# espurna.net
KiCad netlist of a schematic drawn in EAGLE
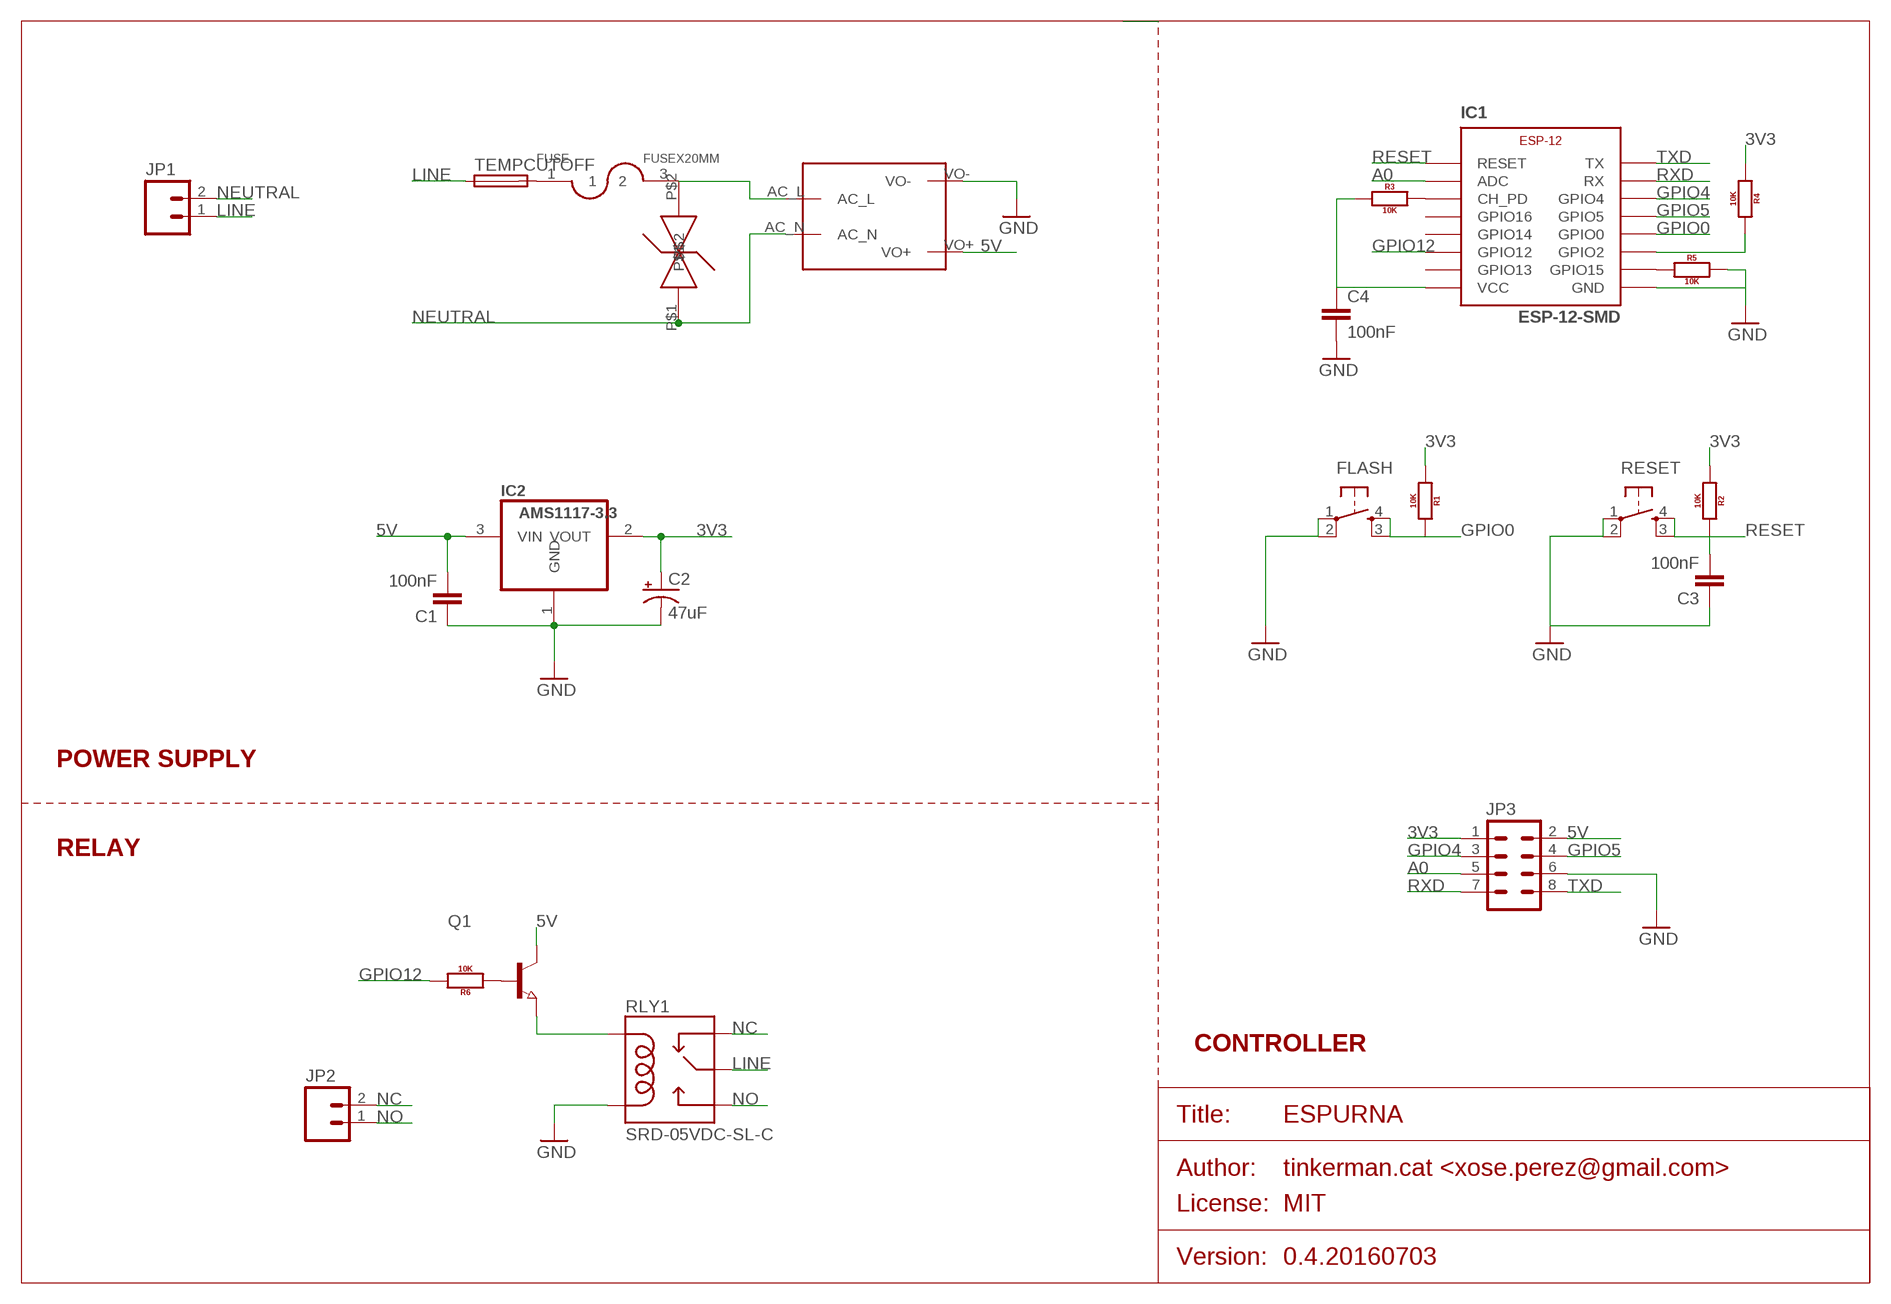
[diagram p0: schematic, sheet 1]

(export (version "E")
  (design (tool "Eeschema 10.0.6"))
  (components
    (comp (ref "C1")
      (value "100nF")
      (footprint "eagle-import:0805")
      (libsource (lib "eagle-import") (part "C-EU0805"))
    )
    (comp (ref "C2")
      (value "47uF")
      (footprint "eagle-import:PANASONIC_C")
      (libsource (lib "eagle-import") (part "CAP_POLC"))
    )
    (comp (ref "C3")
      (value "100nF")
      (footprint "eagle-import:0805")
      (libsource (lib "eagle-import") (part "C-EU0805"))
    )
    (comp (ref "C4")
      (value "100nF")
      (footprint "eagle-import:0805")
      (libsource (lib "eagle-import") (part "C-EU0805"))
    )
    (comp (ref "FLASH")
      (value "TACTILE_BUTTON_SMD")
      (footprint "eagle-import:TACTILE-BUTTON-SMD")
      (libsource (lib "eagle-import") (part "TACTILE_BUTTON_SMD"))
    )
    (comp (ref "FUSE")
      (value "FUSEX20MM")
      (footprint "eagle-import:FUSE_5MM")
      (libsource (lib "eagle-import") (part "FUSEX20MM"))
    )
    (comp (ref "IC1")
      (value "ESP-12-SMD")
      (footprint "eagle-import:ESP-12-SMD")
      (libsource (lib "eagle-import") (part "ESP-12-SMD"))
    )
    (comp (ref "IC2")
      (value "AMS1117-3.3")
      (footprint "eagle-import:SOT223")
      (fields (field (name "MPN") "REG1117"))
      (libsource (lib "eagle-import") (part "REG1117"))
    )
    (comp (ref "JP1")
      (value "M02200MIL")
      (footprint "eagle-import:SCREWTERMINAL-200MIL-2")
      (libsource (lib "eagle-import") (part "M02200MIL"))
    )
    (comp (ref "JP2")
      (value "M02200MIL")
      (footprint "eagle-import:SCREWTERMINAL-200MIL-2")
      (libsource (lib "eagle-import") (part "M02200MIL"))
    )
    (comp (ref "JP3")
      (value "M04X2")
      (footprint "eagle-import:2X4")
      (libsource (lib "eagle-import") (part "M04X2"))
    )
    (comp (ref "Q1")
      (value "NPN-TRANSISTOR_SOT23")
      (footprint "eagle-import:SOT23")
      (libsource (lib "eagle-import") (part "NPN-TRANSISTOR_SOT23"))
    )
    (comp (ref "R1")
      (value "10K")
      (footprint "eagle-import:0805")
      (libsource (lib "eagle-import") (part "RESISTOR0805"))
    )
    (comp (ref "R2")
      (value "10K")
      (footprint "eagle-import:0805")
      (libsource (lib "eagle-import") (part "RESISTOR0805"))
    )
    (comp (ref "R3")
      (value "10K")
      (footprint "eagle-import:0805")
      (libsource (lib "eagle-import") (part "RESISTOR0805"))
    )
    (comp (ref "R4")
      (value "10K")
      (footprint "eagle-import:0805")
      (libsource (lib "eagle-import") (part "RESISTOR0805"))
    )
    (comp (ref "R5")
      (value "10K")
      (footprint "eagle-import:0805")
      (libsource (lib "eagle-import") (part "RESISTOR0805"))
    )
    (comp (ref "R6")
      (value "10K")
      (footprint "eagle-import:0805")
      (libsource (lib "eagle-import") (part "RESISTOR0805"))
    )
    (comp (ref "RESET")
      (value "TACTILE_BUTTON_SMD")
      (footprint "eagle-import:TACTILE-BUTTON-SMD")
      (libsource (lib "eagle-import") (part "TACTILE_BUTTON_SMD"))
    )
    (comp (ref "RLY1")
      (value "SRD-05VDC-SL-C")
      (footprint "eagle-import:SRD-5VDC-SL-C")
      (libsource (lib "eagle-import") (part "RELAYSONGLE"))
    )
    (comp (ref "TEMPCUTOFF")
      (value "PICOFUSE")
      (footprint "eagle-import:PICOFUSE")
      (libsource (lib "eagle-import") (part "PICOFUSE"))
    )
    (comp (ref "U$1")
      (value "MAINS_CONVERTERS")
      (footprint "eagle-import:HLK-PM01")
      (libsource (lib "eagle-import") (part "MAINS_CONVERTERS"))
    )
    (comp (ref "VARISTOR")
      (value "V18ZA2P")
      (footprint "eagle-import:V18ZA2P")
      (libsource (lib "eagle-import") (part "V18ZA2P"))
    )
  )
  (nets
    (net (code "1") (name "/3V3") (class "Default")
      (node (ref "C2") (pin "+") (pinfunction "+_+") (pintype "passive"))
      (node (ref "C4") (pin "1") (pinfunction "1_1") (pintype "passive"))
      (node (ref "IC1") (pin "VCC") (pinfunction "VCC_VCC") (pintype "bidirectional"))
      (node (ref "IC2") (pin "2") (pinfunction "VOUT_2") (pintype "output"))
      (node (ref "JP3") (pin "1") (pinfunction "1_1") (pintype "passive"))
      (node (ref "R1") (pin "1") (pinfunction "1_1") (pintype "passive"))
      (node (ref "R2") (pin "1") (pinfunction "1_1") (pintype "passive"))
      (node (ref "R3") (pin "1") (pinfunction "1_1") (pintype "passive"))
      (node (ref "R4") (pin "1") (pinfunction "1_1") (pintype "passive"))
    )
    (net (code "2") (name "/5V") (class "Default")
      (node (ref "C1") (pin "2") (pinfunction "2_2") (pintype "passive"))
      (node (ref "IC2") (pin "3") (pinfunction "VIN_3") (pintype "input"))
      (node (ref "JP3") (pin "2") (pinfunction "2_2") (pintype "passive"))
      (node (ref "Q1") (pin "3") (pinfunction "C_3") (pintype "passive"))
      (node (ref "U$1") (pin "VO+") (pinfunction "VO+_VO+") (pintype "output"))
    )
    (net (code "3") (name "/A0") (class "Default")
      (node (ref "IC1") (pin "ADC") (pinfunction "ADC_ADC") (pintype "bidirectional"))
      (node (ref "JP3") (pin "5") (pinfunction "5_5") (pintype "passive"))
    )
    (net (code "4") (name "/GPIO0") (class "Default")
      (node (ref "FLASH") (pin "3") (pinfunction "SWB2_3") (pintype "passive"))
      (node (ref "FLASH") (pin "4") (pinfunction "SWA2_4") (pintype "passive"))
      (node (ref "IC1") (pin "GPIO0") (pinfunction "GPIO0_GPIO0") (pintype "bidirectional"))
      (node (ref "R1") (pin "2") (pinfunction "2_2") (pintype "passive"))
    )
    (net (code "5") (name "/GPIO4") (class "Default")
      (node (ref "IC1") (pin "GPIO4") (pinfunction "GPIO4_GPIO4") (pintype "bidirectional"))
      (node (ref "JP3") (pin "3") (pinfunction "3_3") (pintype "passive"))
    )
    (net (code "6") (name "/GPIO5") (class "Default")
      (node (ref "IC1") (pin "GPIO5") (pinfunction "GPIO5_GPIO5") (pintype "bidirectional"))
      (node (ref "JP3") (pin "4") (pinfunction "4_4") (pintype "passive"))
    )
    (net (code "7") (name "/GPIO12") (class "Default")
      (node (ref "IC1") (pin "GPIO12") (pinfunction "GPIO12_GPIO12") (pintype "bidirectional"))
      (node (ref "R6") (pin "2") (pinfunction "2_2") (pintype "passive"))
    )
    (net (code "8") (name "/LINE") (class "Default")
      (node (ref "JP1") (pin "1") (pinfunction "1_1") (pintype "passive"))
      (node (ref "RLY1") (pin "COMMON") (pinfunction "MAIN_COMMON") (pintype "bidirectional"))
      (node (ref "TEMPCUTOFF") (pin "1") (pinfunction "1_1") (pintype "passive"))
    )
    (net (code "9") (name "/NC") (class "Default")
      (node (ref "JP2") (pin "2") (pinfunction "2_2") (pintype "passive"))
      (node (ref "RLY1") (pin "CLOSED") (pinfunction "NC_CLOSED") (pintype "bidirectional"))
    )
    (net (code "10") (name "/NEUTRAL") (class "Default")
      (node (ref "JP1") (pin "2") (pinfunction "2_2") (pintype "passive"))
      (node (ref "U$1") (pin "AC_N") (pinfunction "AC_N_AC_N") (pintype "input"))
      (node (ref "VARISTOR") (pin "P$1") (pinfunction "P$1_P$1") (pintype "bidirectional"))
    )
    (net (code "11") (name "/NO") (class "Default")
      (node (ref "JP2") (pin "1") (pinfunction "1_1") (pintype "passive"))
      (node (ref "RLY1") (pin "OPEN") (pinfunction "NO_OPEN") (pintype "bidirectional"))
    )
    (net (code "12") (name "/RESET") (class "Default")
      (node (ref "C3") (pin "2") (pinfunction "2_2") (pintype "passive"))
      (node (ref "IC1") (pin "RESET") (pinfunction "RESET_RESET") (pintype "bidirectional"))
      (node (ref "R2") (pin "2") (pinfunction "2_2") (pintype "passive"))
      (node (ref "RESET") (pin "3") (pinfunction "SWB2_3") (pintype "passive"))
      (node (ref "RESET") (pin "4") (pinfunction "SWA2_4") (pintype "passive"))
    )
    (net (code "13") (name "/RXD") (class "Default")
      (node (ref "IC1") (pin "RX") (pinfunction "RX_RX") (pintype "bidirectional"))
      (node (ref "JP3") (pin "7") (pinfunction "7_7") (pintype "passive"))
    )
    (net (code "14") (name "/TXD") (class "Default")
      (node (ref "IC1") (pin "TX") (pinfunction "TX_TX") (pintype "bidirectional"))
      (node (ref "JP3") (pin "8") (pinfunction "8_8") (pintype "passive"))
    )
    (net (code "15") (name "GND") (class "Default")
      (node (ref "C1") (pin "1") (pinfunction "1_1") (pintype "passive"))
      (node (ref "C2") (pin "-") (pinfunction "-_-") (pintype "passive"))
      (node (ref "C3") (pin "1") (pinfunction "1_1") (pintype "passive"))
      (node (ref "C4") (pin "2") (pinfunction "2_2") (pintype "passive"))
      (node (ref "FLASH") (pin "1") (pinfunction "SWA1_1") (pintype "passive"))
      (node (ref "FLASH") (pin "2") (pinfunction "SWB1_2") (pintype "passive"))
      (node (ref "IC1") (pin "GND") (pinfunction "GND_GND") (pintype "bidirectional"))
      (node (ref "IC2") (pin "1") (pinfunction "GND_1") (pintype "power_in"))
      (node (ref "JP3") (pin "6") (pinfunction "6_6") (pintype "passive"))
      (node (ref "R5") (pin "2") (pinfunction "2_2") (pintype "passive"))
      (node (ref "RESET") (pin "1") (pinfunction "SWA1_1") (pintype "passive"))
      (node (ref "RESET") (pin "2") (pinfunction "SWB1_2") (pintype "passive"))
      (node (ref "RLY1") (pin "COIL2") (pinfunction "COIL2_COIL2") (pintype "bidirectional"))
      (node (ref "U$1") (pin "VO-") (pinfunction "VO-_VO-") (pintype "output"))
    )
    (net (code "16") (name "Net-(FUSE-2)") (class "Default")
      (node (ref "FUSE") (pin "3") (pinfunction "2_3") (pintype "bidirectional"))
      (node (ref "U$1") (pin "AC_L") (pinfunction "AC_L_AC_L") (pintype "input"))
      (node (ref "VARISTOR") (pin "P$2") (pinfunction "P$2_P$2") (pintype "bidirectional"))
    )
    (net (code "17") (name "Net-(FUSE-Pad1)") (class "Default")
      (node (ref "FUSE") (pin "1") (pinfunction "1_1") (pintype "bidirectional"))
      (node (ref "TEMPCUTOFF") (pin "2") (pinfunction "2_2") (pintype "passive"))
    )
    (net (code "18") (name "Net-(IC1-PadCH_PD)") (class "Default")
      (node (ref "IC1") (pin "CH_PD") (pinfunction "CH_PD_CH_PD") (pintype "bidirectional"))
      (node (ref "R3") (pin "2") (pinfunction "2_2") (pintype "passive"))
    )
    (net (code "19") (name "Net-(IC1-PadGPIO2)") (class "Default")
      (node (ref "IC1") (pin "GPIO2") (pinfunction "GPIO2_GPIO2") (pintype "bidirectional"))
      (node (ref "R4") (pin "2") (pinfunction "2_2") (pintype "passive"))
    )
    (net (code "20") (name "Net-(IC1-PadGPIO15)") (class "Default")
      (node (ref "IC1") (pin "GPIO15") (pinfunction "GPIO15_GPIO15") (pintype "bidirectional"))
      (node (ref "R5") (pin "1") (pinfunction "1_1") (pintype "passive"))
    )
    (net (code "21") (name "Net-(Q1-B)") (class "Default")
      (node (ref "Q1") (pin "1") (pinfunction "B_1") (pintype "passive"))
      (node (ref "R6") (pin "1") (pinfunction "1_1") (pintype "passive"))
    )
    (net (code "22") (name "Net-(Q1-E)") (class "Default")
      (node (ref "Q1") (pin "2") (pinfunction "E_2") (pintype "passive"))
      (node (ref "RLY1") (pin "COIL1") (pinfunction "COIL1_COIL1") (pintype "bidirectional"))
    )
    (net (code "23") (name "unconnected-(IC1-PadGPIO13)") (class "Default")
      (node (ref "IC1") (pin "GPIO13") (pinfunction "GPIO13_GPIO13") (pintype "bidirectional"))
    )
    (net (code "24") (name "unconnected-(IC1-PadGPIO14)") (class "Default")
      (node (ref "IC1") (pin "GPIO14") (pinfunction "GPIO14_GPIO14") (pintype "bidirectional"))
    )
    (net (code "25") (name "unconnected-(IC1-PadGPIO16)") (class "Default")
      (node (ref "IC1") (pin "GPIO16") (pinfunction "GPIO16_GPIO16") (pintype "bidirectional"))
    )
  )
)
